# eeZeeVGA.net
KiCad netlist of a schematic drawn in EAGLE
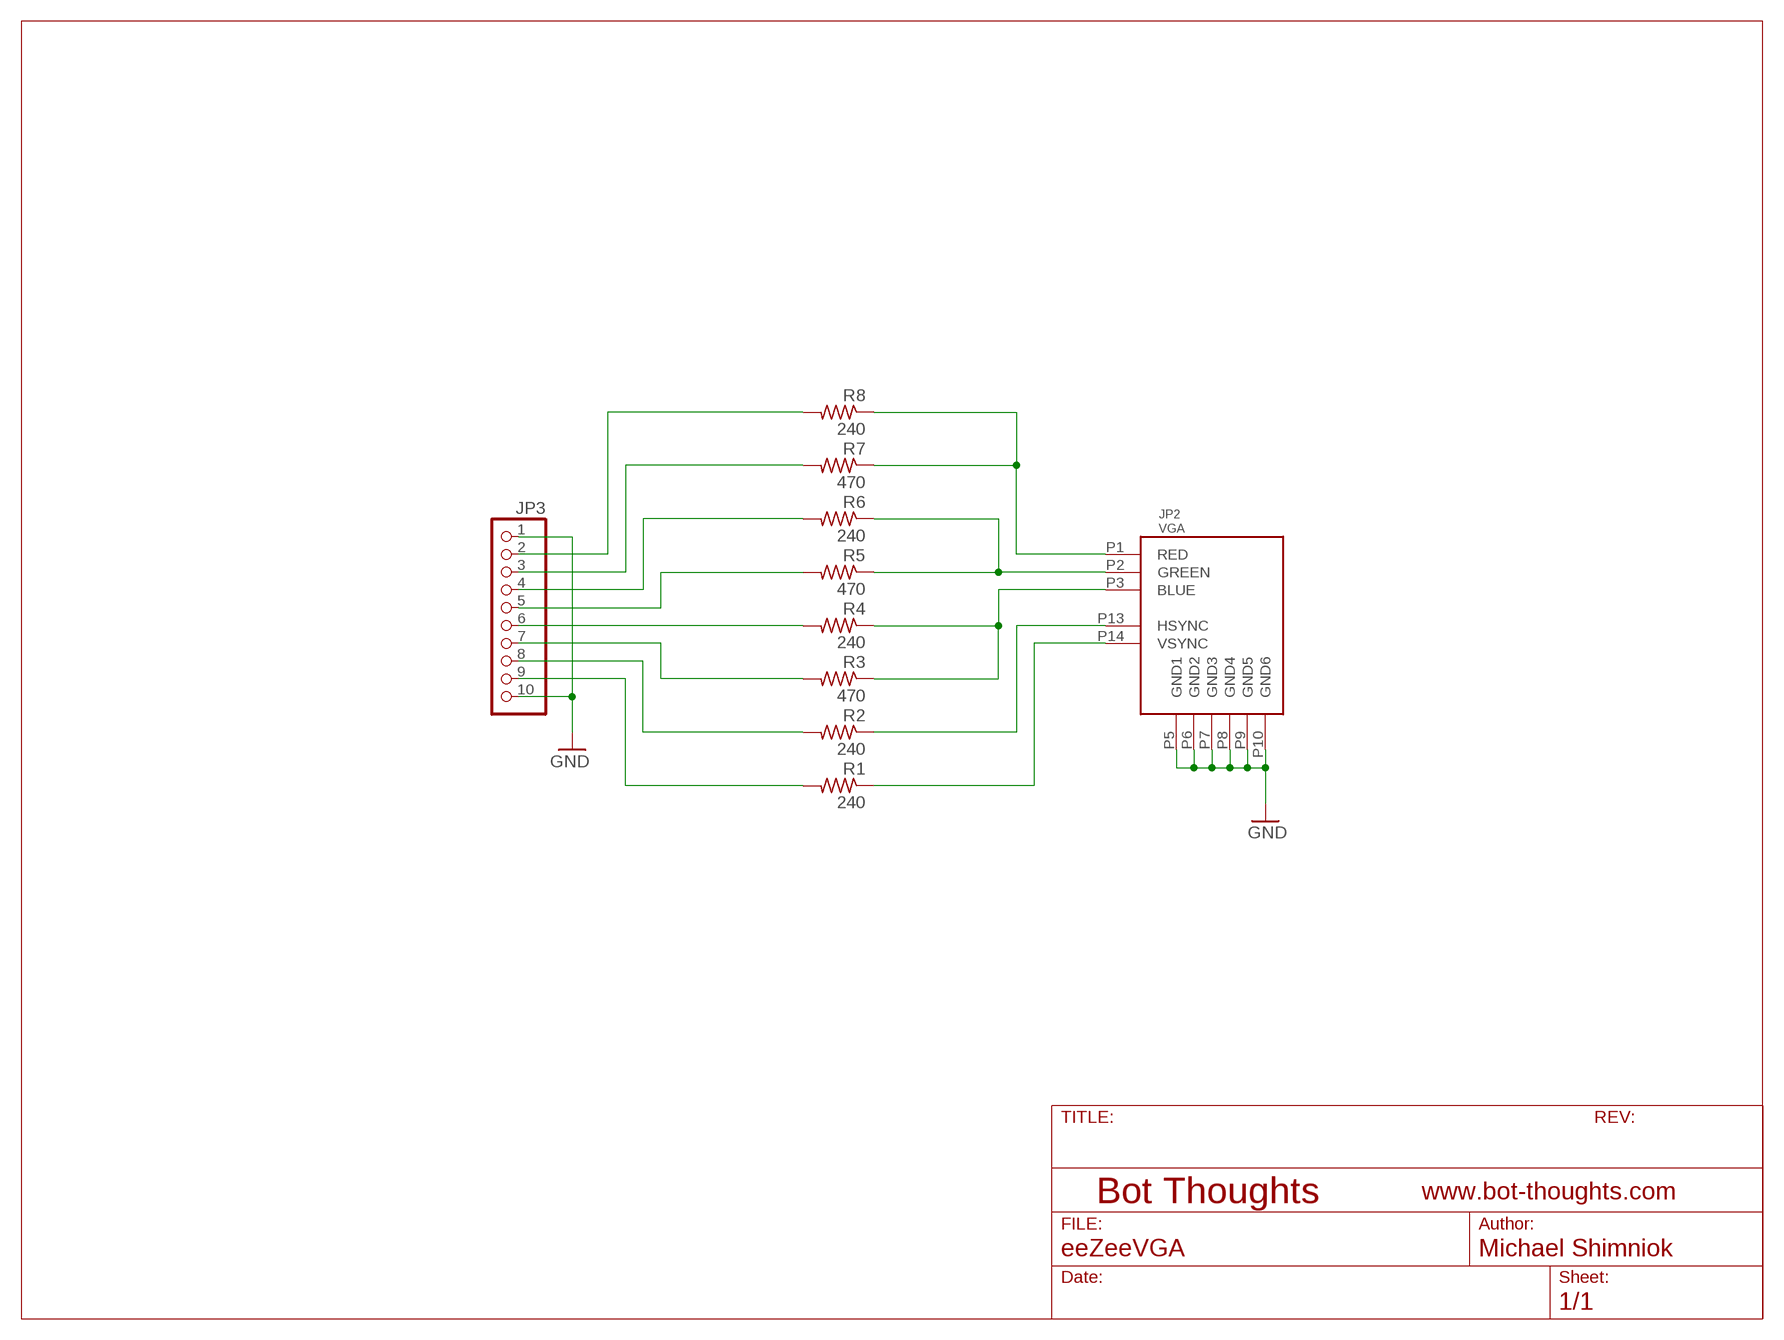
[diagram p0: schematic, sheet 1]

(export (version "E")
  (design (tool "Eeschema 10.0.6"))
  (components
    (comp (ref "JP2")
      (value "VGA")
      (footprint "eagle-import:FCI_DSUB_HD_15_RA")
      (libsource (lib "eagle-import") (part "VGA"))
    )
    (comp (ref "JP3")
      (value "PINHD-1X10_2.54-S")
      (footprint "eagle-import:1X10-S")
      (libsource (lib "eagle-import") (part "PINHD-1X10_2.54-S"))
    )
    (comp (ref "R1")
      (value "240")
      (footprint "eagle-import:R0603")
      (libsource (lib "eagle-import") (part "R-US_R0603"))
    )
    (comp (ref "R2")
      (value "240")
      (footprint "eagle-import:R0603")
      (libsource (lib "eagle-import") (part "R-US_R0603"))
    )
    (comp (ref "R3")
      (value "470")
      (footprint "eagle-import:R0603")
      (libsource (lib "eagle-import") (part "R-US_R0603"))
    )
    (comp (ref "R4")
      (value "240")
      (footprint "eagle-import:R0603")
      (libsource (lib "eagle-import") (part "R-US_R0603"))
    )
    (comp (ref "R5")
      (value "470")
      (footprint "eagle-import:R0603")
      (libsource (lib "eagle-import") (part "R-US_R0603"))
    )
    (comp (ref "R6")
      (value "240")
      (footprint "eagle-import:R0603")
      (libsource (lib "eagle-import") (part "R-US_R0603"))
    )
    (comp (ref "R7")
      (value "470")
      (footprint "eagle-import:R0603")
      (libsource (lib "eagle-import") (part "R-US_R0603"))
    )
    (comp (ref "R8")
      (value "240")
      (footprint "eagle-import:R0603")
      (libsource (lib "eagle-import") (part "R-US_R0603"))
    )
  )
  (nets
    (net (code "1") (name "GND") (class "Default")
      (node (ref "JP2") (pin "P10") (pinfunction "GND6_P10") (pintype "bidirectional"))
      (node (ref "JP2") (pin "P5") (pinfunction "GND1_P5") (pintype "bidirectional"))
      (node (ref "JP2") (pin "P6") (pinfunction "GND2_P6") (pintype "bidirectional"))
      (node (ref "JP2") (pin "P7") (pinfunction "GND3_P7") (pintype "bidirectional"))
      (node (ref "JP2") (pin "P8") (pinfunction "GND4_P8") (pintype "bidirectional"))
      (node (ref "JP2") (pin "P9") (pinfunction "GND5_P9") (pintype "bidirectional"))
      (node (ref "JP3") (pin "1") (pinfunction "1_1") (pintype "passive"))
      (node (ref "JP3") (pin "10") (pinfunction "10_10") (pintype "passive"))
    )
    (net (code "2") (name "Net-(JP2-BLUE)") (class "Default")
      (node (ref "JP2") (pin "P3") (pinfunction "BLUE_P3") (pintype "bidirectional"))
      (node (ref "R3") (pin "1") (pinfunction "1_1") (pintype "passive"))
      (node (ref "R4") (pin "1") (pinfunction "1_1") (pintype "passive"))
    )
    (net (code "3") (name "Net-(JP2-GREEN)") (class "Default")
      (node (ref "JP2") (pin "P2") (pinfunction "GREEN_P2") (pintype "bidirectional"))
      (node (ref "R5") (pin "1") (pinfunction "1_1") (pintype "passive"))
      (node (ref "R6") (pin "1") (pinfunction "1_1") (pintype "passive"))
    )
    (net (code "4") (name "Net-(JP2-HSYNC)") (class "Default")
      (node (ref "JP2") (pin "P13") (pinfunction "HSYNC_P13") (pintype "bidirectional"))
      (node (ref "R2") (pin "1") (pinfunction "1_1") (pintype "passive"))
    )
    (net (code "5") (name "Net-(JP2-RED)") (class "Default")
      (node (ref "JP2") (pin "P1") (pinfunction "RED_P1") (pintype "bidirectional"))
      (node (ref "R7") (pin "1") (pinfunction "1_1") (pintype "passive"))
      (node (ref "R8") (pin "1") (pinfunction "1_1") (pintype "passive"))
    )
    (net (code "6") (name "Net-(JP2-VSYNC)") (class "Default")
      (node (ref "JP2") (pin "P14") (pinfunction "VSYNC_P14") (pintype "bidirectional"))
      (node (ref "R1") (pin "1") (pinfunction "1_1") (pintype "passive"))
    )
    (net (code "7") (name "Net-(JP3-Pad2)") (class "Default")
      (node (ref "JP3") (pin "2") (pinfunction "2_2") (pintype "passive"))
      (node (ref "R8") (pin "2") (pinfunction "2_2") (pintype "passive"))
    )
    (net (code "8") (name "Net-(JP3-Pad3)") (class "Default")
      (node (ref "JP3") (pin "3") (pinfunction "3_3") (pintype "passive"))
      (node (ref "R7") (pin "2") (pinfunction "2_2") (pintype "passive"))
    )
    (net (code "9") (name "Net-(JP3-Pad4)") (class "Default")
      (node (ref "JP3") (pin "4") (pinfunction "4_4") (pintype "passive"))
      (node (ref "R6") (pin "2") (pinfunction "2_2") (pintype "passive"))
    )
    (net (code "10") (name "Net-(JP3-Pad5)") (class "Default")
      (node (ref "JP3") (pin "5") (pinfunction "5_5") (pintype "passive"))
      (node (ref "R5") (pin "2") (pinfunction "2_2") (pintype "passive"))
    )
    (net (code "11") (name "Net-(JP3-Pad6)") (class "Default")
      (node (ref "JP3") (pin "6") (pinfunction "6_6") (pintype "passive"))
      (node (ref "R4") (pin "2") (pinfunction "2_2") (pintype "passive"))
    )
    (net (code "12") (name "Net-(JP3-Pad7)") (class "Default")
      (node (ref "JP3") (pin "7") (pinfunction "7_7") (pintype "passive"))
      (node (ref "R3") (pin "2") (pinfunction "2_2") (pintype "passive"))
    )
    (net (code "13") (name "Net-(JP3-Pad8)") (class "Default")
      (node (ref "JP3") (pin "8") (pinfunction "8_8") (pintype "passive"))
      (node (ref "R2") (pin "2") (pinfunction "2_2") (pintype "passive"))
    )
    (net (code "14") (name "Net-(JP3-Pad9)") (class "Default")
      (node (ref "JP3") (pin "9") (pinfunction "9_9") (pintype "passive"))
      (node (ref "R1") (pin "2") (pinfunction "2_2") (pintype "passive"))
    )
  )
)
